# Sheet1.net
KiCad netlist of a schematic drawn in Altium Designer
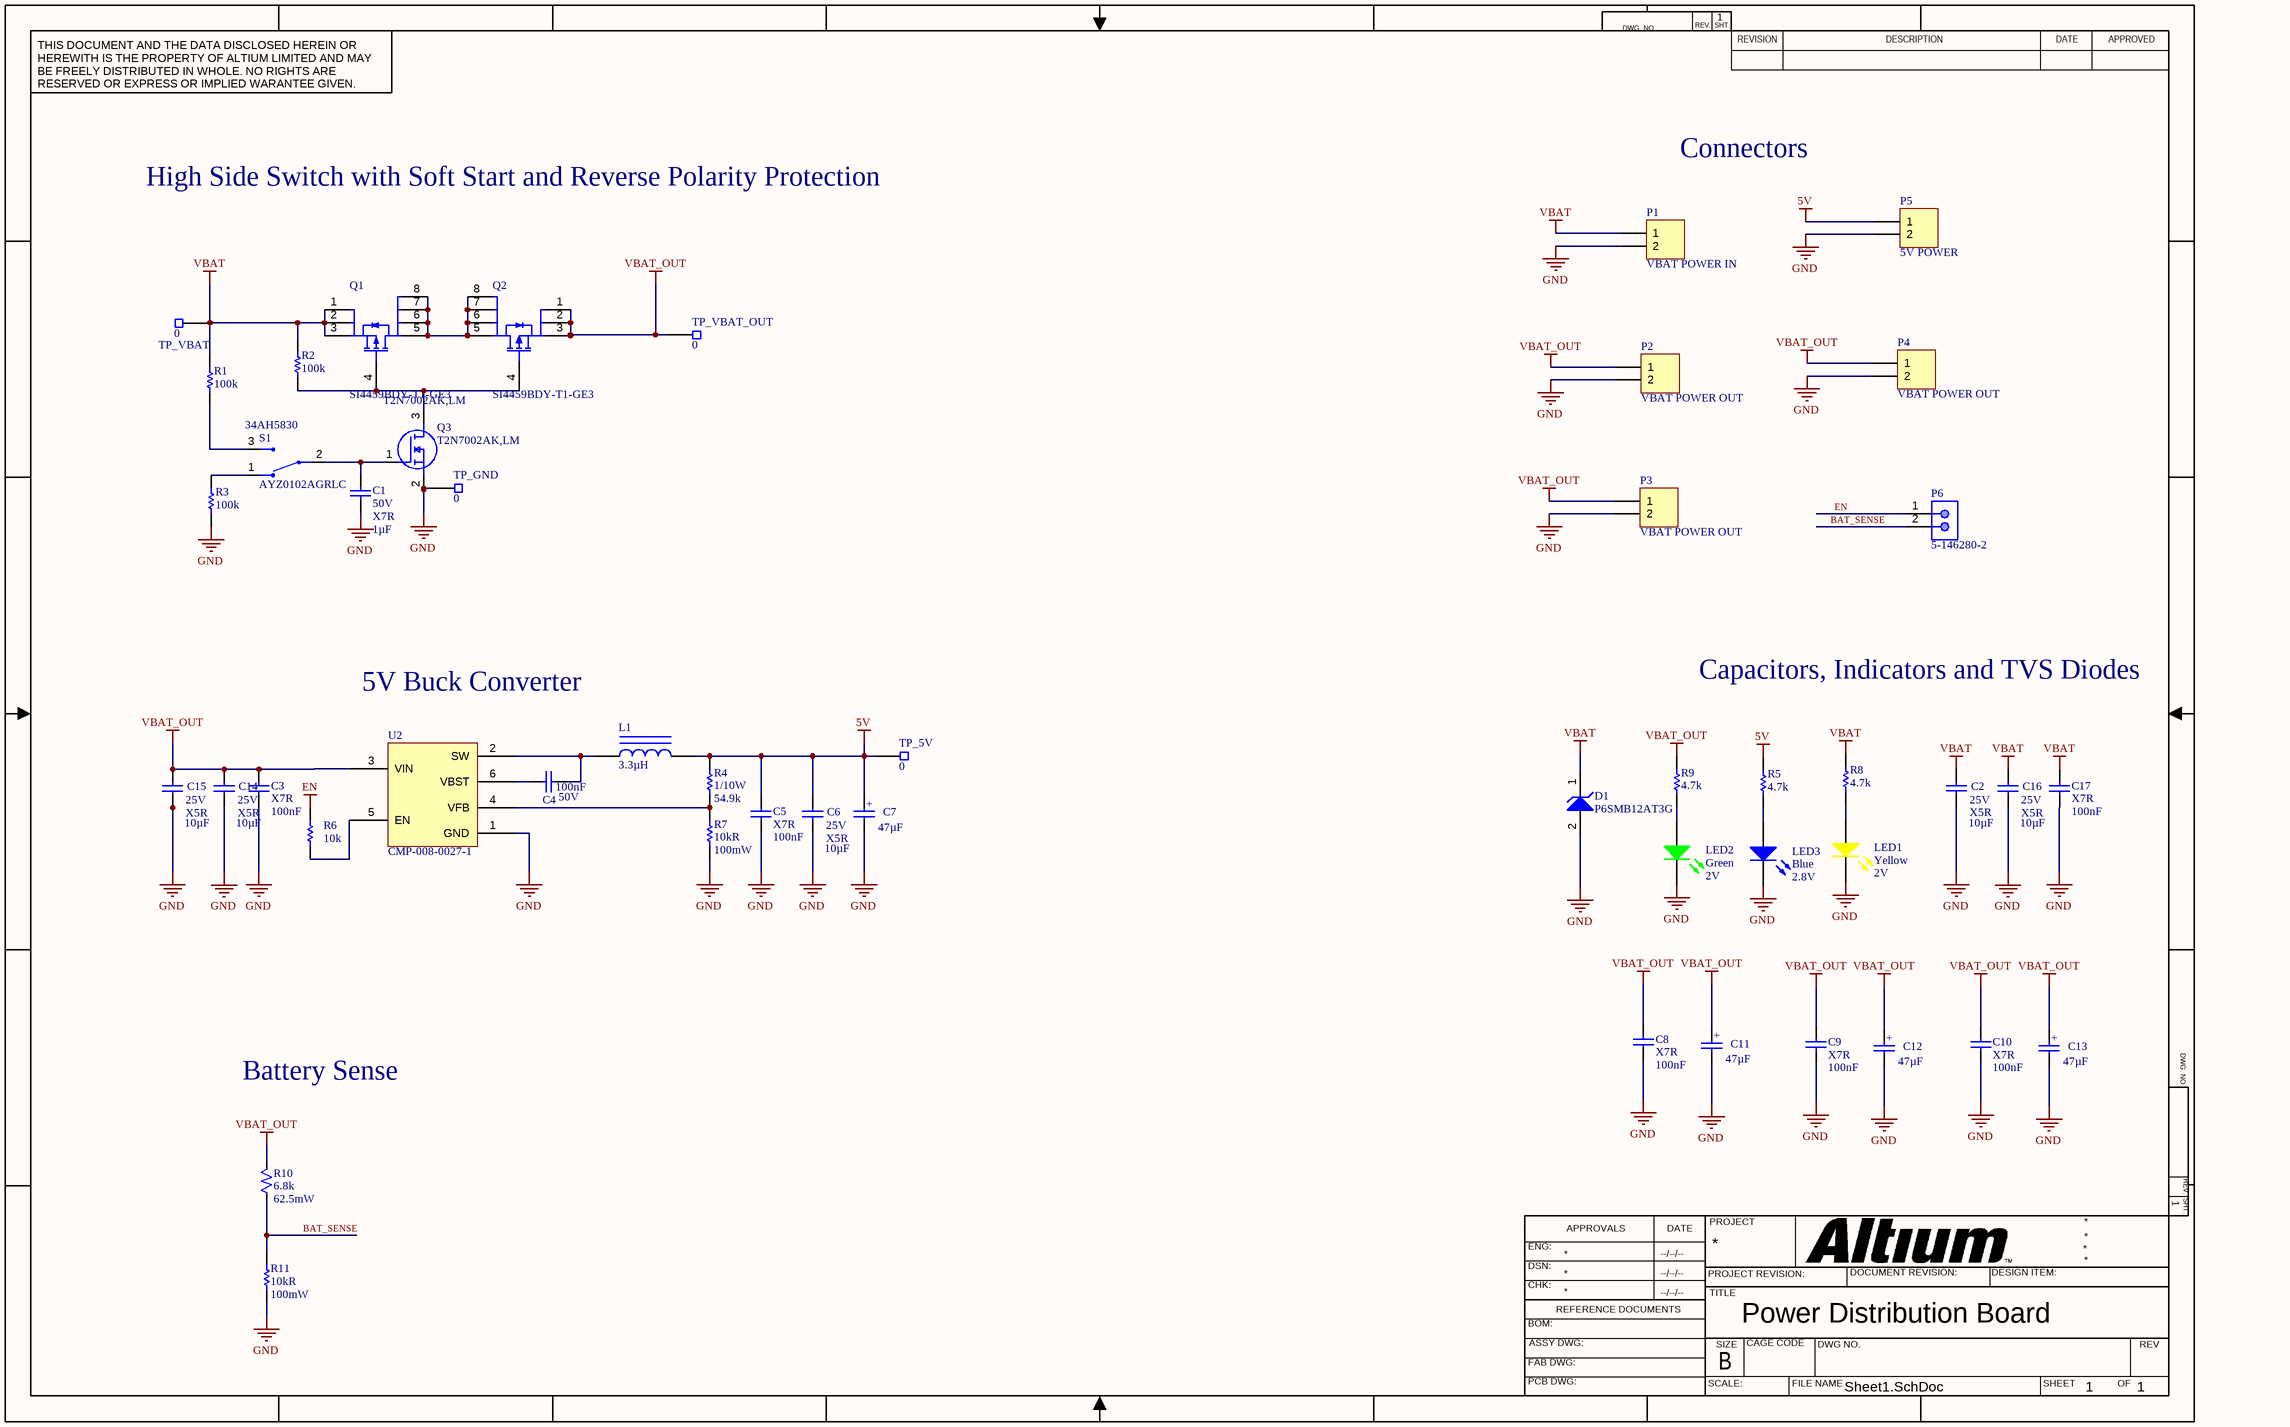
[diagram p0: Sheet1.SchDoc]

(export (version "E")
  (design (tool "Eeschema 10.0.6"))
  (components
    (comp (ref "C1")
      (value "1µF")
      (footprint "CAP, 0603")
      (description "1µF ±10% 50V Ceramic Capacitor X7R 0603 (1608 Metric)")
      (fields
        (field (name "VOLTAGE") "50V")
        (field (name "TEMPERATURE COEFFICIENT") "X7R")
        (field (name "TOLERANCE") "10%")
        (field (name "Comment") "CAP CER 1UF 50V 10% X7R 0603")
        (field (name "SOURCE") "Schematic Diagrams.SchLib")
      )
      (libsource (lib "") (part "Symbol_1"))
    )
    (comp (ref "C2")
      (value "10µF")
      (footprint "CAP, 0603")
      (description "10µF ±20% 25V Ceramic Capacitor X5R 0603 (1608 Metric)")
      (fields
        (field (name "TOLERANCE") "20%")
        (field (name "VOLTAGE") "25V")
        (field (name "TEMPERATURE COEFFICIENT") "X5R")
        (field (name "Comment") "CMP-013-0018-1")
        (field (name "SOURCE") "Schematic Diagrams.SchLib")
      )
      (libsource (lib "") (part "Symbol_1"))
    )
    (comp (ref "C3")
      (value "100nF")
      (footprint "FP-GCJ188-0_2-IPC_C")
      (description "CAP CER 0.1UF 50V X7R 0603")
      (fields
        (field (name "TOLERANCE") "10%")
        (field (name "TEMPERATURE COEFFICIENT") "X7R")
        (field (name "Comment") "CAP_0.1UF_50V_X7R_0603")
      )
      (libsource (lib "University of Waterloo - Solar Car Team") (part "CAP"))
    )
    (comp (ref "C4")
      (value "100nF")
      (footprint "CAP, 0603")
      (description "0.10µF ±10% 50V Ceramic Capacitor X7R 0603 (1608 Metric)")
      (fields
        (field (name "TOLERANCE") "10%")
        (field (name "VOLTAGE") "50V")
        (field (name "Comment") "CMP-013-0022-3")
        (field (name "SOURCE") "Schematic Diagrams.SchLib")
      )
      (libsource (lib "") (part "Symbol_1"))
    )
    (comp (ref "C5")
      (value "100nF")
      (footprint "FP-GCJ188-0_2-IPC_C")
      (description "CAP CER 0.1UF 50V X7R 0603")
      (fields
        (field (name "TOLERANCE") "10%")
        (field (name "TEMPERATURE COEFFICIENT") "X7R")
        (field (name "Comment") "CAP_0.1UF_50V_X7R_0603")
      )
      (libsource (lib "University of Waterloo - Solar Car Team") (part "CAP"))
    )
    (comp (ref "C6")
      (value "10µF")
      (footprint "CAP, 0603")
      (description "10µF ±20% 25V Ceramic Capacitor X5R 0603 (1608 Metric)")
      (fields
        (field (name "TOLERANCE") "20%")
        (field (name "VOLTAGE") "25V")
        (field (name "TEMPERATURE COEFFICIENT") "X5R")
        (field (name "Comment") "CMP-013-0018-1")
        (field (name "SOURCE") "Schematic Diagrams.SchLib")
      )
      (libsource (lib "") (part "Symbol_1"))
    )
    (comp (ref "C7")
      (value "47µF")
      (footprint "CAP ALUM 6.3MM RADIAL SMD")
      (description "47µF 35V Aluminum Electrolytic Capacitors Radial, Can - SMD 1000 Hrs @ 85°C")
      (fields
        (field (name "TOLERANCE") "20%")
        (field (name "Comment") "CMP-013-0000-3")
        (field (name "SOURCE") "Schematic Diagrams.SchLib")
      )
      (libsource (lib "University of Waterloo - Solar Car Team") (part "Symbol"))
    )
    (comp (ref "C8")
      (value "100nF")
      (footprint "FP-GCJ188-0_2-IPC_C")
      (description "CAP CER 0.1UF 50V X7R 0603")
      (fields
        (field (name "TOLERANCE") "10%")
        (field (name "TEMPERATURE COEFFICIENT") "X7R")
        (field (name "Comment") "CAP_0.1UF_50V_X7R_0603")
      )
      (libsource (lib "University of Waterloo - Solar Car Team") (part "CAP"))
    )
    (comp (ref "C9")
      (value "100nF")
      (footprint "FP-GCJ188-0_2-IPC_C")
      (description "CAP CER 0.1UF 50V X7R 0603")
      (fields
        (field (name "TOLERANCE") "10%")
        (field (name "TEMPERATURE COEFFICIENT") "X7R")
        (field (name "Comment") "CAP_0.1UF_50V_X7R_0603")
      )
      (libsource (lib "University of Waterloo - Solar Car Team") (part "CAP"))
    )
    (comp (ref "C10")
      (value "100nF")
      (footprint "FP-GCJ188-0_2-IPC_C")
      (description "CAP CER 0.1UF 50V X7R 0603")
      (fields
        (field (name "TOLERANCE") "10%")
        (field (name "TEMPERATURE COEFFICIENT") "X7R")
        (field (name "Comment") "CAP_0.1UF_50V_X7R_0603")
      )
      (libsource (lib "University of Waterloo - Solar Car Team") (part "CAP"))
    )
    (comp (ref "C11")
      (value "47µF")
      (footprint "CAP ALUM 6.3MM RADIAL SMD")
      (description "47µF 35V Aluminum Electrolytic Capacitors Radial, Can - SMD 1000 Hrs @ 85°C")
      (fields
        (field (name "TOLERANCE") "20%")
        (field (name "Comment") "CMP-013-0000-3")
        (field (name "SOURCE") "Schematic Diagrams.SchLib")
      )
      (libsource (lib "University of Waterloo - Solar Car Team") (part "Symbol"))
    )
    (comp (ref "C12")
      (value "47µF")
      (footprint "CAP ALUM 6.3MM RADIAL SMD")
      (description "47µF 35V Aluminum Electrolytic Capacitors Radial, Can - SMD 1000 Hrs @ 85°C")
      (fields
        (field (name "TOLERANCE") "20%")
        (field (name "Comment") "CMP-013-0000-3")
        (field (name "SOURCE") "Schematic Diagrams.SchLib")
      )
      (libsource (lib "University of Waterloo - Solar Car Team") (part "Symbol"))
    )
    (comp (ref "C13")
      (value "47µF")
      (footprint "CAP ALUM 6.3MM RADIAL SMD")
      (description "47µF 35V Aluminum Electrolytic Capacitors Radial, Can - SMD 1000 Hrs @ 85°C")
      (fields
        (field (name "TOLERANCE") "20%")
        (field (name "Comment") "CMP-013-0000-3")
        (field (name "SOURCE") "Schematic Diagrams.SchLib")
      )
      (libsource (lib "University of Waterloo - Solar Car Team") (part "Symbol"))
    )
    (comp (ref "C14")
      (value "10µF")
      (footprint "CAP, 0603")
      (description "10µF ±20% 25V Ceramic Capacitor X5R 0603 (1608 Metric)")
      (fields
        (field (name "TOLERANCE") "20%")
        (field (name "VOLTAGE") "25V")
        (field (name "TEMPERATURE COEFFICIENT") "X5R")
        (field (name "Comment") "CMP-013-0018-1")
        (field (name "SOURCE") "Schematic Diagrams.SchLib")
      )
      (libsource (lib "") (part "Symbol_1"))
    )
    (comp (ref "C15")
      (value "10µF")
      (footprint "CAP, 0603")
      (description "10µF ±20% 25V Ceramic Capacitor X5R 0603 (1608 Metric)")
      (fields
        (field (name "TOLERANCE") "20%")
        (field (name "VOLTAGE") "25V")
        (field (name "TEMPERATURE COEFFICIENT") "X5R")
        (field (name "Comment") "CMP-013-0018-1")
        (field (name "SOURCE") "Schematic Diagrams.SchLib")
      )
      (libsource (lib "") (part "Symbol_1"))
    )
    (comp (ref "C16")
      (value "10µF")
      (footprint "CAP, 0603")
      (description "10µF ±20% 25V Ceramic Capacitor X5R 0603 (1608 Metric)")
      (fields
        (field (name "TOLERANCE") "20%")
        (field (name "VOLTAGE") "25V")
        (field (name "TEMPERATURE COEFFICIENT") "X5R")
        (field (name "Comment") "CMP-013-0018-1")
        (field (name "SOURCE") "Schematic Diagrams.SchLib")
      )
      (libsource (lib "") (part "Symbol_1"))
    )
    (comp (ref "C17")
      (value "100nF")
      (footprint "FP-GCJ188-0_2-IPC_C")
      (description "CAP CER 0.1UF 50V X7R 0603")
      (fields
        (field (name "TOLERANCE") "10%")
        (field (name "TEMPERATURE COEFFICIENT") "X7R")
        (field (name "Comment") "CAP_0.1UF_50V_X7R_0603")
      )
      (libsource (lib "University of Waterloo - Solar Car Team") (part "CAP"))
    )
    (comp (ref "D1")
      (value "P6SMB12AT3G")
      (footprint "ONSC-SMB-2-403A-03_J_V")
      (fields (field (name "MANUFACTURER") "On Semiconductor"))
      (libsource (lib "Altium Content Vault") (part "ONSC-K1A2-2"))
    )
    (comp (ref "L1")
      (value "CMP-009-0008-2")
      (footprint "IND 3.3UH 5.2A 20 MOHM SMD VLP8040")
      (description "3.3µH Shielded Wirewound Inductor 5.2A 20 mOhm Max Nonstandard")
      (fields
        (field (name "TOLERANCE") "20%")
        (field (name "INDUCTANCE") "3.3µH")
        (field (name "SOURCE") "Schematic Diagrams.SchLib")
      )
      (libsource (lib "") (part "Symbol_3"))
    )
    (comp (ref "LED1")
      (value "LED YELLOW CLEAR 2.1V 0603")
      (footprint "LED_0603")
      (description "Yellow 590nm LED Indication - Discrete 2V 0603 (1608 Metric)")
      (fields
        (field (name "COLOR") "Yellow")
        (field (name "VOLTAGE - FORWARD (VF) (TYP)") "2V")
        (field (name "MANUFACTURER PART NUMBER") "150060YS75000")
        (field (name "MANUFACTURER") "Wurth Electronics Inc.")
        (field (name "SOURCE") "Schematic Diagrams.SchLib")
      )
      (libsource (lib "University of Waterloo - Solar Car Team") (part "LED YELLOW CLEAR 2.1V 0603"))
    )
    (comp (ref "LED2")
      (value "LED GREEN CLEAR 2V 0603")
      (footprint "LED_0603")
      (description "Green 572nm LED Indication - Discrete 2V 0603 (1608 Metric)")
      (fields
        (field (name "COLOR") "Green")
        (field (name "VOLTAGE - FORWARD (VF) (TYP)") "2V")
        (field (name "MANUFACTURER") "Wurth Electronics Inc.")
        (field (name "MANUFACTURER PART NUMBER") "150060VS75000")
        (field (name "SOURCE") "Schematic Diagrams.SchLib")
      )
      (libsource (lib "University of Waterloo - Solar Car Team") (part "LED GREEN CLEAR 2V 0603"))
    )
    (comp (ref "LED3")
      (value "LED BLUE CLEAR 2.8V 0603")
      (footprint "LED_0603")
      (description "Blue 470nm LED Indication - Discrete 2.8V 0603 (1608 Metric)")
      (fields
        (field (name "COLOR") "Blue")
        (field (name "VOLTAGE - FORWARD (VF) (TYP)") "2.8V")
        (field (name "SOURCE") "Schematic Diagrams.SchLib")
      )
      (libsource (lib "University of Waterloo - Solar Car Team") (part "LED BLUE CLEAR 2.8V 0603"))
    )
    (comp (ref "P1")
      (value "VBAT POWER IN")
      (footprint "B2B-XH")
      (description "1x2 Pin Header")
      (libsource (lib "FYDP") (part "1x2 Header"))
    )
    (comp (ref "P2")
      (value "VBAT POWER OUT")
      (footprint "B2B-XH")
      (description "1x2 Pin Header")
      (libsource (lib "FYDP") (part "1x2 Header"))
    )
    (comp (ref "P3")
      (value "VBAT POWER OUT")
      (footprint "B2B-XH")
      (description "1x2 Pin Header")
      (libsource (lib "FYDP") (part "1x2 Header"))
    )
    (comp (ref "P4")
      (value "VBAT POWER OUT")
      (footprint "B2B-XH")
      (description "1x2 Pin Header")
      (libsource (lib "FYDP") (part "1x2 Header"))
    )
    (comp (ref "P5")
      (value "5V POWER")
      (footprint "B2B-XH")
      (description "1x2 Pin Header")
      (libsource (lib "FYDP") (part "1x2 Header"))
    )
    (comp (ref "P6")
      (value "5-146280-2")
      (footprint "TECO-5-146280-2_V")
      (fields (field (name "MANUFACTURER") "TE Connectivity"))
      (libsource (lib "Altium Content Vault") (part "CN-1P-M-R2"))
    )
    (comp (ref "Q1")
      (value "SI4459BDY-T1-GE3")
      (footprint "SI4459BDY-T1-GE3-Footprint-1")
      (description "Small Signal Field-Effect Transistor")
      (libsource (lib "University of Waterloo - Solar Car Team") (part "New symbol 1"))
    )
    (comp (ref "Q2")
      (value "SI4459BDY-T1-GE3")
      (footprint "SI4459BDY-T1-GE3-Footprint-1")
      (description "Small Signal Field-Effect Transistor")
      (libsource (lib "University of Waterloo - Solar Car Team") (part "New symbol 1"))
    )
    (comp (ref "Q3")
      (value "T2N7002AK,LM")
      (footprint "SamacSys:TBAT54CLM")
      (description "MOSFET (N-Channel)")
      (fields
        (field (name "MOUSER PART NUMBER") "757-T2N7002AKLM")
        (field (name "SUPPLIER PART NUMBER 1") "T2N7002AK,LM")
      )
      (libsource (lib "*") (part "T2N7002AK,LM"))
    )
    (comp (ref "R1")
      (value "100k")
      (footprint "RESC1608X55X25ML10T15")
      (description "Chip Resistor, 100 KOhm, +/- 1%, 0.1 W, -55 to 155 degC, 0603 (1608 Metric)")
      (fields (field (name "POWER") "100mW") (field (name "TOLERANCE") "1%"))
      (libsource (lib "University of Waterloo - Solar Car Team") (part "RES-2"))
    )
    (comp (ref "R2")
      (value "100k")
      (footprint "RESC1608X55X25ML10T15")
      (description "Chip Resistor, 100 KOhm, +/- 1%, 0.1 W, -55 to 155 degC, 0603 (1608 Metric)")
      (fields (field (name "POWER") "100mW") (field (name "TOLERANCE") "1%"))
      (libsource (lib "University of Waterloo - Solar Car Team") (part "RES-2"))
    )
    (comp (ref "R3")
      (value "100k")
      (footprint "RESC1608X55X25ML10T15")
      (description "Chip Resistor, 100 KOhm, +/- 1%, 0.1 W, -55 to 155 degC, 0603 (1608 Metric)")
      (fields (field (name "POWER") "100mW") (field (name "TOLERANCE") "1%"))
      (libsource (lib "University of Waterloo - Solar Car Team") (part "RES-2"))
    )
    (comp (ref "R4")
      (value "CMP-010-0030-1")
      (footprint "RES, 0603")
      (description "54.9k Ohm ±1% 0.1W, 1/10W Chip Resistor 0603 (1608 Metric) Automotive AEC-Q200 Thick Film")
      (fields
        (field (name "MANUFACTURER") "Panasonic Electronic Components")
        (field (name "TOLERANCE") "1%")
        (field (name "POWER (WATTS)") "1/10W")
        (field (name "RESISTANCE (OHMS)") "54.9k")
        (field (name "SOURCE") "Schematic Diagrams.SchLib")
      )
      (libsource (lib "") (part "Symbol_2"))
    )
    (comp (ref "R5")
      (value "RES 4.7K OHM 1% 1/10W 0603")
      (footprint "RES, 0603")
      (description "4.7k Ohm ±1% 0.1W, 1/10W Chip Resistor 0603 (1608 Metric) Moisture Resistant Thick Film")
      (fields
        (field (name "RESISTANCE") "4.7k")
        (field (name "TOLERANCE") "1%")
        (field (name "SOURCE") "Schematic Diagrams.SchLib")
      )
      (libsource (lib "") (part "Symbol_2"))
    )
    (comp (ref "R6")
      (value "RES SMD 10K OHM 1% 1/10W 0603")
      (footprint "RESC1609X50X30ML8T20")
      (fields (field (name "TOLERANCE") "1%") (field (name "RESISTANCE") "10k"))
      (libsource (lib "University of Waterloo - Solar Car Team") (part "RES-2"))
    )
    (comp (ref "R7")
      (value "RES SMD 10K OHM 1% 1/10W 0603")
      (footprint "RESC1609X50X30ML8T20")
      (fields
        (field (name "TOLERANCE") "1%")
        (field (name "RESISTANCE") "10kR")
        (field (name "RATED POWER DISSIPATION (P)") "100mW")
      )
      (libsource (lib "University of Waterloo - Solar Car Team") (part "RES-2"))
    )
    (comp (ref "R8")
      (value "RES 4.7K OHM 1% 1/10W 0603")
      (footprint "RES, 0603")
      (description "4.7k Ohm ±1% 0.1W, 1/10W Chip Resistor 0603 (1608 Metric) Moisture Resistant Thick Film")
      (fields
        (field (name "RESISTANCE") "4.7k")
        (field (name "TOLERANCE") "1%")
        (field (name "SOURCE") "Schematic Diagrams.SchLib")
      )
      (libsource (lib "") (part "Symbol_2"))
    )
    (comp (ref "R9")
      (value "RES 4.7K OHM 1% 1/10W 0603")
      (footprint "RES, 0603")
      (description "4.7k Ohm ±1% 0.1W, 1/10W Chip Resistor 0603 (1608 Metric) Moisture Resistant Thick Film")
      (fields
        (field (name "RESISTANCE") "4.7k")
        (field (name "TOLERANCE") "1%")
        (field (name "SOURCE") "Schematic Diagrams.SchLib")
      )
      (libsource (lib "") (part "Symbol_2"))
    )
    (comp (ref "R10")
      (value "6.8k")
      (footprint "RES 0402")
      (fields
        (field (name "TOLERANCE") "5%")
        (field (name "RATED POWER DISSIPATION (P)") "62.5mW")
        (field (name "MANUFACTURER PART NUMBER") "RC0402JR-076K8L")
        (field (name "MANUFACTURER") "Yageo")
      )
      (libsource (lib "University of Waterloo - Solar Car Team") (part "RES 88.7K OHM 1% 1/10W 0603"))
    )
    (comp (ref "R11")
      (value "RES SMD 10K OHM 1% 1/10W 0603")
      (footprint "RESC1609X50X30ML8T20")
      (fields
        (field (name "TOLERANCE") "1%")
        (field (name "RESISTANCE") "10kR")
        (field (name "RATED POWER DISSIPATION (P)") "100mW")
      )
      (libsource (lib "University of Waterloo - Solar Car Team") (part "RES-2"))
    )
    (comp (ref "S1")
      (value "AYZ0102AGRLC")
      (footprint "SnapEDApcb:SW_AYZ0102AGRLC")
      (description "Slide Switch SPDT Surface Mount, Right Angle")
      (fields
        (field (name "DIGI-KEY_PART_NUMBER") "401-2012-1-ND")
        (field (name "MF") "C&K")
        (field (name "SUPPLIER PART NUMBER 1") "34AH5830")
      )
      (libsource (lib "SnapEDAsch") (part "AYZ0102AGRLC"))
    )
    (comp (ref "TP_5V")
      (value "Test Point 0603 SMD")
      (footprint "TEST POINT 0603 SMD")
      (fields (field (name "RESISTANCE") "0") (field (name "SOURCE") "Schematic Diagrams.SchLib"))
      (libsource (lib "University of Waterloo - Solar Car Team") (part "Test Point 0603 SMD"))
    )
    (comp (ref "TP_GND")
      (value "Test Point 0603 SMD")
      (footprint "TEST POINT 0603 SMD")
      (fields (field (name "RESISTANCE") "0") (field (name "SOURCE") "Schematic Diagrams.SchLib"))
      (libsource (lib "University of Waterloo - Solar Car Team") (part "Test Point 0603 SMD"))
    )
    (comp (ref "TP_VBAT")
      (value "Test Point 0603 SMD")
      (footprint "TEST POINT 0603 SMD")
      (fields (field (name "RESISTANCE") "0") (field (name "SOURCE") "Schematic Diagrams.SchLib"))
      (libsource (lib "University of Waterloo - Solar Car Team") (part "Test Point 0603 SMD"))
    )
    (comp (ref "TP_VBAT_OUT")
      (value "Test Point 0603 SMD")
      (footprint "TEST POINT 0603 SMD")
      (fields (field (name "RESISTANCE") "0") (field (name "SOURCE") "Schematic Diagrams.SchLib"))
      (libsource (lib "University of Waterloo - Solar Car Team") (part "Test Point 0603 SMD"))
    )
    (comp (ref "U2")
      (value "CMP-008-0027-1")
      (footprint "IC REG BUCK 4.5V TO 17V, 5A")
      (description "Buck Switching Regulator IC Positive Adjustable 0.6V 1 Output 5A SOT-23-6 Thin, TSOT-23-6")
      (fields
        (field (name "MANUFACTURER") "Texas Instruments")
        (field (name "MANUFACTURER PART NUMBER") "TPS565201DDCT")
        (field (name "SOURCE") "Schematic Diagrams.SchLib")
      )
      (libsource (lib "University of Waterloo - Solar Car Team") (part "IC REG BUCK 4.5V TO 17V, 5A, SYNCHRONOUS STE"))
    )
  )
  (nets
    (net (code "1") (name "/BAT_SENSE") (class "Default")
      (node (ref "P6") (pin "2") (pinfunction "2_2") (pintype "passive"))
      (node (ref "R10") (pin "1") (pintype "passive"))
      (node (ref "R11") (pin "2") (pinfunction "2_2") (pintype "passive"))
    )
    (net (code "2") (name "5V") (class "Default")
      (node (ref "C5") (pin "2") (pinfunction "2_2") (pintype "passive"))
      (node (ref "C6") (pin "1") (pinfunction "1_1") (pintype "passive"))
      (node (ref "C7") (pin "1") (pinfunction "1_1") (pintype "passive"))
      (node (ref "L1") (pin "2") (pinfunction "2_2") (pintype "passive"))
      (node (ref "P5") (pin "1") (pinfunction "1_1") (pintype "passive"))
      (node (ref "R4") (pin "1") (pinfunction "1_1") (pintype "passive"))
      (node (ref "R5") (pin "1") (pinfunction "1_1") (pintype "passive"))
      (node (ref "TP_5V") (pin "1") (pinfunction "1_1") (pintype "passive"))
    )
    (net (code "3") (name "EN") (class "Default")
      (node (ref "P6") (pin "1") (pinfunction "1_1") (pintype "passive"))
      (node (ref "R6") (pin "2") (pinfunction "2_2") (pintype "passive"))
    )
    (net (code "4") (name "GND") (class "Default")
      (node (ref "C1") (pin "2") (pinfunction "2_2") (pintype "passive"))
      (node (ref "C10") (pin "1") (pinfunction "1_1") (pintype "passive"))
      (node (ref "C11") (pin "2") (pinfunction "2_2") (pintype "passive"))
      (node (ref "C12") (pin "2") (pinfunction "2_2") (pintype "passive"))
      (node (ref "C13") (pin "2") (pinfunction "2_2") (pintype "passive"))
      (node (ref "C14") (pin "2") (pinfunction "2_2") (pintype "passive"))
      (node (ref "C15") (pin "2") (pinfunction "2_2") (pintype "passive"))
      (node (ref "C16") (pin "2") (pinfunction "2_2") (pintype "passive"))
      (node (ref "C17") (pin "1") (pinfunction "1_1") (pintype "passive"))
      (node (ref "C2") (pin "2") (pinfunction "2_2") (pintype "passive"))
      (node (ref "C3") (pin "1") (pinfunction "1_1") (pintype "passive"))
      (node (ref "C5") (pin "1") (pinfunction "1_1") (pintype "passive"))
      (node (ref "C6") (pin "2") (pinfunction "2_2") (pintype "passive"))
      (node (ref "C7") (pin "2") (pinfunction "2_2") (pintype "passive"))
      (node (ref "C8") (pin "1") (pinfunction "1_1") (pintype "passive"))
      (node (ref "C9") (pin "1") (pinfunction "1_1") (pintype "passive"))
      (node (ref "D1") (pin "2") (pinfunction "A_2") (pintype "passive"))
      (node (ref "LED1") (pin "2") (pinfunction "K_2") (pintype "passive"))
      (node (ref "LED2") (pin "2") (pinfunction "K_2") (pintype "passive"))
      (node (ref "LED3") (pin "2") (pinfunction "K_2") (pintype "passive"))
      (node (ref "P1") (pin "2") (pinfunction "2_2") (pintype "passive"))
      (node (ref "P2") (pin "2") (pinfunction "2_2") (pintype "passive"))
      (node (ref "P3") (pin "2") (pinfunction "2_2") (pintype "passive"))
      (node (ref "P4") (pin "2") (pinfunction "2_2") (pintype "passive"))
      (node (ref "P5") (pin "2") (pinfunction "2_2") (pintype "passive"))
      (node (ref "Q3") (pin "2") (pinfunction "S_2") (pintype "passive"))
      (node (ref "R11") (pin "1") (pinfunction "1_1") (pintype "passive"))
      (node (ref "R3") (pin "1") (pinfunction "1_1") (pintype "passive"))
      (node (ref "R7") (pin "1") (pinfunction "1_1") (pintype "passive"))
      (node (ref "TP_GND") (pin "1") (pinfunction "1_1") (pintype "passive"))
      (node (ref "U2") (pin "1") (pinfunction "GND_1") (pintype "passive"))
    )
    (net (code "5") (name "Net-(LED1-A)") (class "Default")
      (node (ref "LED1") (pin "1") (pinfunction "A_1") (pintype "passive"))
      (node (ref "R8") (pin "2") (pinfunction "2_2") (pintype "passive"))
    )
    (net (code "6") (name "Net-(LED2-A)") (class "Default")
      (node (ref "LED2") (pin "1") (pinfunction "A_1") (pintype "passive"))
      (node (ref "R9") (pin "2") (pinfunction "2_2") (pintype "passive"))
    )
    (net (code "7") (name "Net-(LED3-A)") (class "Default")
      (node (ref "LED3") (pin "1") (pinfunction "A_1") (pintype "passive"))
      (node (ref "R5") (pin "2") (pinfunction "2_2") (pintype "passive"))
    )
    (net (code "8") (name "Net-(Q1-D-Pad5)") (class "Default")
      (node (ref "Q1") (pin "5") (pinfunction "D_5") (pintype "passive"))
      (node (ref "Q1") (pin "6") (pinfunction "D_6") (pintype "passive"))
      (node (ref "Q1") (pin "7") (pinfunction "D_7") (pintype "passive"))
      (node (ref "Q1") (pin "8") (pinfunction "D_8") (pintype "passive"))
      (node (ref "Q2") (pin "5") (pinfunction "D_5") (pintype "passive"))
      (node (ref "Q2") (pin "6") (pinfunction "D_6") (pintype "passive"))
      (node (ref "Q2") (pin "7") (pinfunction "D_7") (pintype "passive"))
      (node (ref "Q2") (pin "8") (pinfunction "D_8") (pintype "passive"))
    )
    (net (code "9") (name "Net-(Q1-G)") (class "Default")
      (node (ref "Q1") (pin "4") (pinfunction "G_4") (pintype "passive"))
      (node (ref "Q2") (pin "4") (pinfunction "G_4") (pintype "passive"))
      (node (ref "Q3") (pin "3") (pinfunction "D_3") (pintype "passive"))
      (node (ref "R2") (pin "1") (pinfunction "1_1") (pintype "passive"))
    )
    (net (code "10") (name "Net-(Q3-G)") (class "Default")
      (node (ref "C1") (pin "1") (pinfunction "1_1") (pintype "passive"))
      (node (ref "Q3") (pin "1") (pinfunction "G_1") (pintype "passive"))
      (node (ref "S1") (pin "2") (pinfunction "2_2") (pintype "passive"))
    )
    (net (code "11") (name "Net-(R1-Pad1)") (class "Default")
      (node (ref "R1") (pin "1") (pinfunction "1_1") (pintype "passive"))
      (node (ref "S1") (pin "3") (pinfunction "3_3") (pintype "passive"))
    )
    (net (code "12") (name "Net-(R3-Pad2)") (class "Default")
      (node (ref "R3") (pin "2") (pinfunction "2_2") (pintype "passive"))
      (node (ref "S1") (pin "1") (pinfunction "1_1") (pintype "passive"))
    )
    (net (code "13") (name "Net-(U2-EN)") (class "Default")
      (node (ref "R6") (pin "1") (pinfunction "1_1") (pintype "passive"))
      (node (ref "U2") (pin "5") (pinfunction "EN_5") (pintype "passive"))
    )
    (net (code "14") (name "Net-(U2-SW)") (class "Default")
      (node (ref "C4") (pin "2") (pinfunction "2_2") (pintype "passive"))
      (node (ref "L1") (pin "1") (pinfunction "1_1") (pintype "passive"))
      (node (ref "U2") (pin "2") (pinfunction "SW_2") (pintype "passive"))
    )
    (net (code "15") (name "Net-(U2-VBST)") (class "Default")
      (node (ref "C4") (pin "1") (pinfunction "1_1") (pintype "passive"))
      (node (ref "U2") (pin "6") (pinfunction "VBST_6") (pintype "passive"))
    )
    (net (code "16") (name "Net-(U2-VFB)") (class "Default")
      (node (ref "R4") (pin "2") (pinfunction "2_2") (pintype "passive"))
      (node (ref "R7") (pin "2") (pinfunction "2_2") (pintype "passive"))
      (node (ref "U2") (pin "4") (pinfunction "VFB_4") (pintype "passive"))
    )
    (net (code "17") (name "VBAT") (class "Default")
      (node (ref "C16") (pin "1") (pinfunction "1_1") (pintype "passive"))
      (node (ref "C17") (pin "2") (pinfunction "2_2") (pintype "passive"))
      (node (ref "C2") (pin "1") (pinfunction "1_1") (pintype "passive"))
      (node (ref "D1") (pin "1") (pinfunction "K_1") (pintype "passive"))
      (node (ref "P1") (pin "1") (pinfunction "1_1") (pintype "passive"))
      (node (ref "Q1") (pin "1") (pinfunction "S_1") (pintype "passive"))
      (node (ref "Q1") (pin "2") (pinfunction "S_2") (pintype "passive"))
      (node (ref "Q1") (pin "3") (pinfunction "S_3") (pintype "passive"))
      (node (ref "R1") (pin "2") (pinfunction "2_2") (pintype "passive"))
      (node (ref "R2") (pin "2") (pinfunction "2_2") (pintype "passive"))
      (node (ref "R8") (pin "1") (pinfunction "1_1") (pintype "passive"))
    )
    (net (code "18") (name "VBAT_OUT") (class "Default")
      (node (ref "C10") (pin "2") (pinfunction "2_2") (pintype "passive"))
      (node (ref "C11") (pin "1") (pinfunction "1_1") (pintype "passive"))
      (node (ref "C12") (pin "1") (pinfunction "1_1") (pintype "passive"))
      (node (ref "C13") (pin "1") (pinfunction "1_1") (pintype "passive"))
      (node (ref "C14") (pin "1") (pinfunction "1_1") (pintype "passive"))
      (node (ref "C15") (pin "1") (pinfunction "1_1") (pintype "passive"))
      (node (ref "C3") (pin "2") (pinfunction "2_2") (pintype "passive"))
      (node (ref "C8") (pin "2") (pinfunction "2_2") (pintype "passive"))
      (node (ref "C9") (pin "2") (pinfunction "2_2") (pintype "passive"))
      (node (ref "P2") (pin "1") (pinfunction "1_1") (pintype "passive"))
      (node (ref "P3") (pin "1") (pinfunction "1_1") (pintype "passive"))
      (node (ref "P4") (pin "1") (pinfunction "1_1") (pintype "passive"))
      (node (ref "Q2") (pin "1") (pinfunction "S_1") (pintype "passive"))
      (node (ref "Q2") (pin "2") (pinfunction "S_2") (pintype "passive"))
      (node (ref "Q2") (pin "3") (pinfunction "S_3") (pintype "passive"))
      (node (ref "R10") (pin "2") (pintype "passive"))
      (node (ref "R9") (pin "1") (pinfunction "1_1") (pintype "passive"))
      (node (ref "TP_VBAT_OUT") (pin "1") (pinfunction "1_1") (pintype "passive"))
      (node (ref "U2") (pin "3") (pinfunction "VIN_3") (pintype "passive"))
    )
    (net (code "19") (name "unconnected-(TP_VBAT-Pad1)") (class "Default")
      (node (ref "TP_VBAT") (pin "1") (pinfunction "1_1") (pintype "passive"))
    )
  )
)
